# main.net
KiCad netlist of a schematic drawn in EAGLE
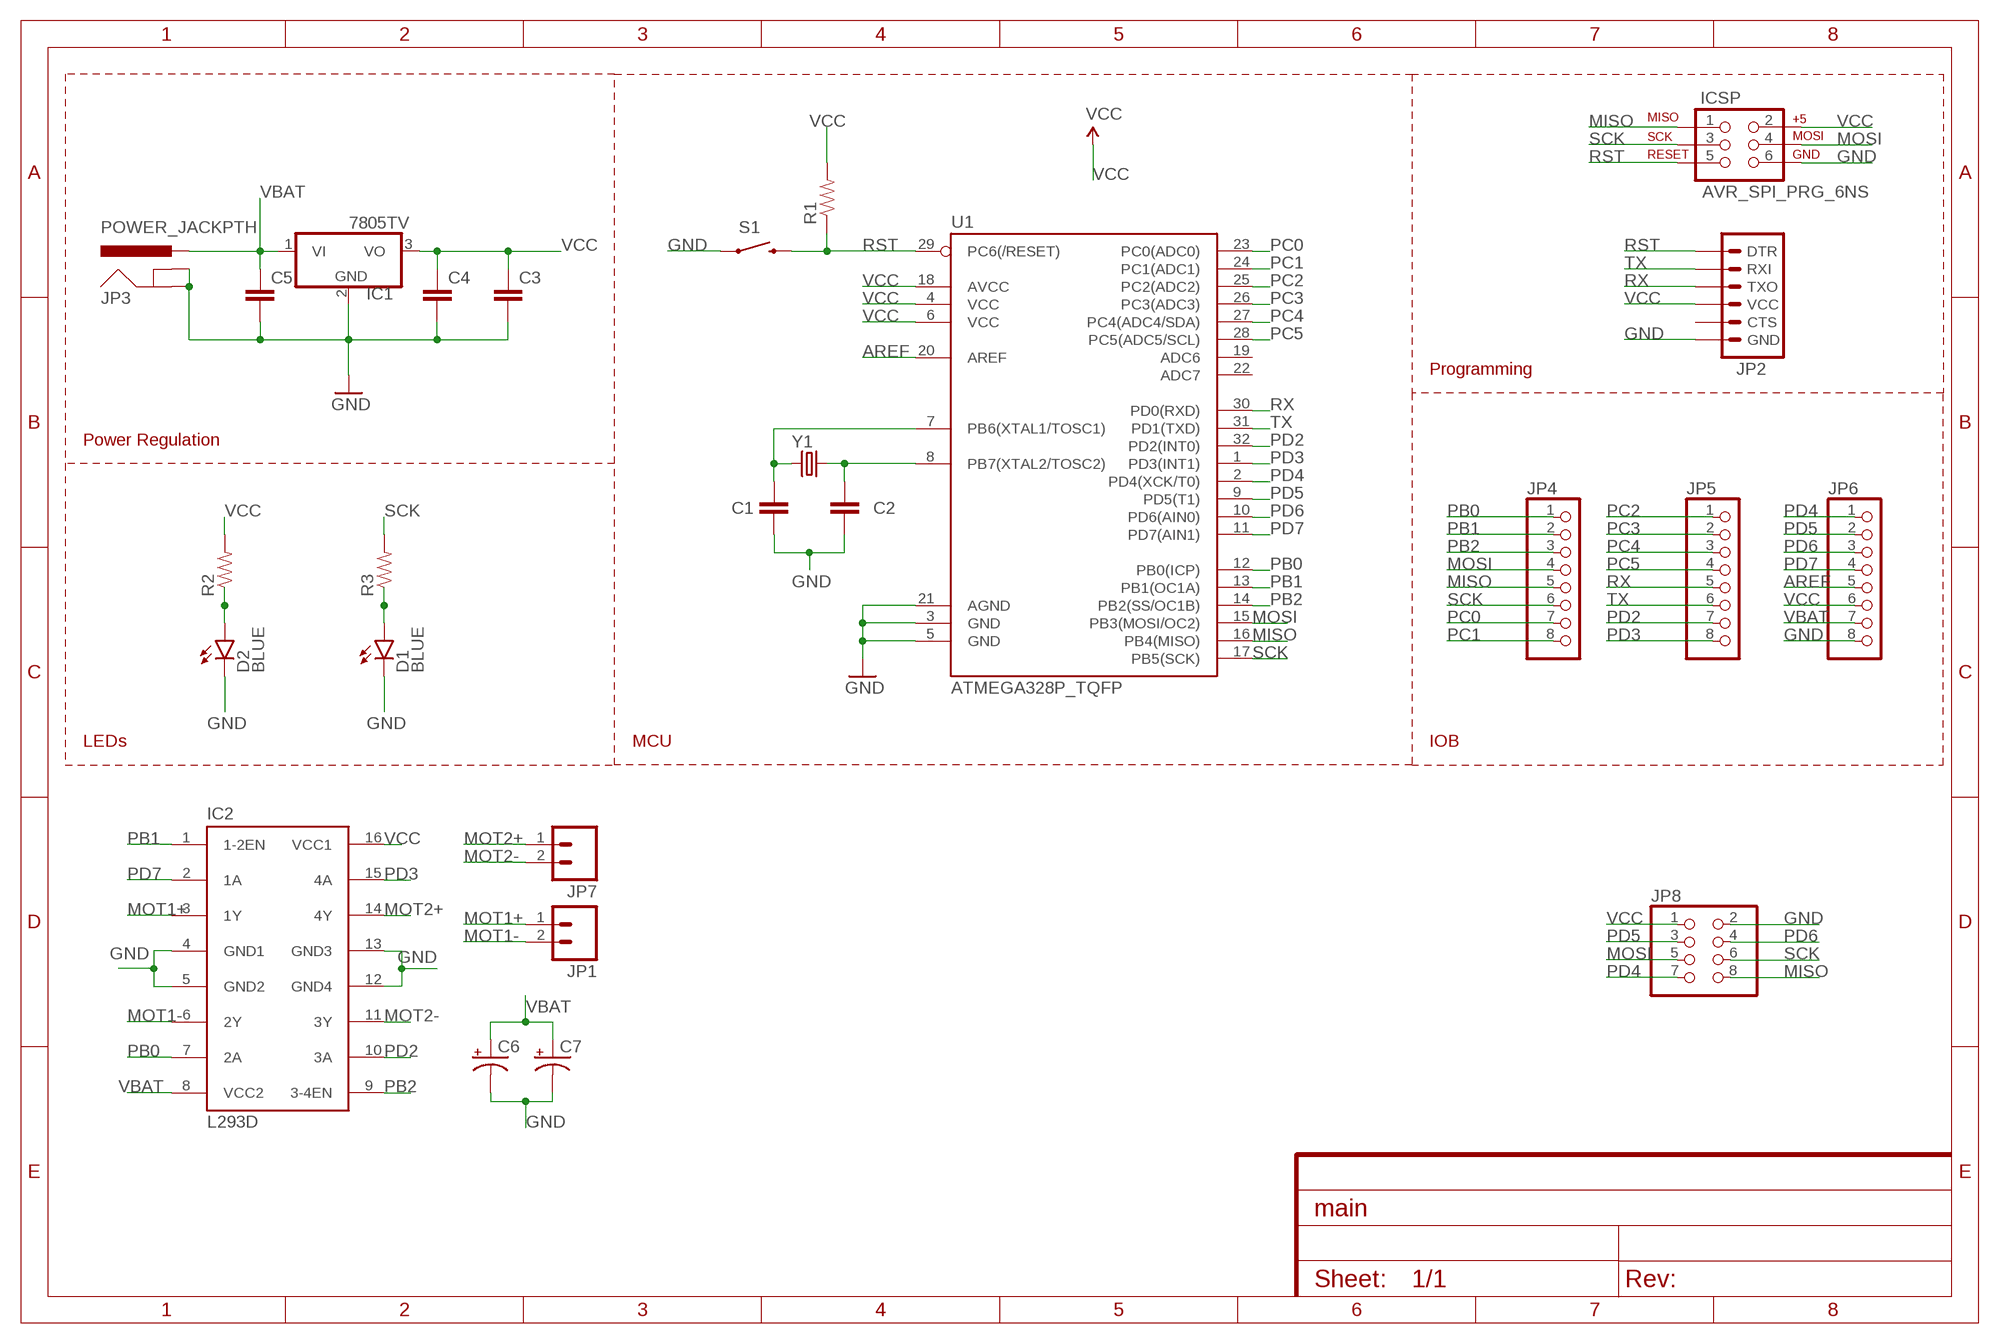
[diagram p0: schematic, sheet 1]

(export (version "E")
  (design (tool "Eeschema 10.0.6"))
  (components
    (comp (ref "C1")
      (value "CAP0805")
      (footprint "eagle-import:0805")
      (libsource (lib "eagle-import") (part "CAP0805"))
    )
    (comp (ref "C2")
      (value "CAP0805")
      (footprint "eagle-import:0805")
      (libsource (lib "eagle-import") (part "CAP0805"))
    )
    (comp (ref "C3")
      (value "CAP0805")
      (footprint "eagle-import:0805")
      (libsource (lib "eagle-import") (part "CAP0805"))
    )
    (comp (ref "C4")
      (value "CAP0805")
      (footprint "eagle-import:0805")
      (libsource (lib "eagle-import") (part "CAP0805"))
    )
    (comp (ref "C5")
      (value "CAP0805")
      (footprint "eagle-import:0805")
      (libsource (lib "eagle-import") (part "CAP0805"))
    )
    (comp (ref "C6")
      (value "CAP_POLPTH2")
      (footprint "eagle-import:CPOL-RADIAL-10UF-25V")
      (libsource (lib "eagle-import") (part "CAP_POLPTH2"))
    )
    (comp (ref "C7")
      (value "CAP_POLPTH2")
      (footprint "eagle-import:CPOL-RADIAL-10UF-25V")
      (libsource (lib "eagle-import") (part "CAP_POLPTH2"))
    )
    (comp (ref "D1")
      (value "BLUE")
      (footprint "eagle-import:LED-0603")
      (libsource (lib "eagle-import") (part "LED-BLUE0603"))
    )
    (comp (ref "D2")
      (value "BLUE")
      (footprint "eagle-import:LED-0603")
      (libsource (lib "eagle-import") (part "LED-BLUE0603"))
    )
    (comp (ref "IC1")
      (value "7805TV")
      (footprint "eagle-import:TO220V")
      (libsource (lib "eagle-import") (part "78TV05"))
    )
    (comp (ref "IC2")
      (value "L293D")
      (footprint "eagle-import:DIL16")
      (libsource (lib "eagle-import") (part "L293D"))
    )
    (comp (ref "ICSP")
      (value "AVR_SPI_PRG_6NS")
      (footprint "eagle-import:2X3-NS")
      (libsource (lib "eagle-import") (part "AVR_SPI_PRG_6NS"))
    )
    (comp (ref "JP1")
      (value "M025MM")
      (footprint "eagle-import:SCREWTERMINAL-5MM-2")
      (libsource (lib "eagle-import") (part "M025MM"))
    )
    (comp (ref "JP2")
      (value "ARDUINO_SERIAL_PROGRAMLOCK")
      (footprint "eagle-import:1X06_LOCK")
      (libsource (lib "eagle-import") (part "ARDUINO_SERIAL_PROGRAMLOCK"))
    )
    (comp (ref "JP3")
      (value "POWER_JACKPTH")
      (footprint "eagle-import:POWER_JACK_PTH")
      (libsource (lib "eagle-import") (part "POWER_JACKPTH"))
    )
    (comp (ref "JP4")
      (value "PINHD-1X8")
      (footprint "eagle-import:1X08")
      (libsource (lib "eagle-import") (part "PINHD-1X8"))
    )
    (comp (ref "JP5")
      (value "PINHD-1X8")
      (footprint "eagle-import:1X08")
      (libsource (lib "eagle-import") (part "PINHD-1X8"))
    )
    (comp (ref "JP6")
      (value "PINHD-1X8")
      (footprint "eagle-import:1X08")
      (libsource (lib "eagle-import") (part "PINHD-1X8"))
    )
    (comp (ref "JP7")
      (value "M025MM")
      (footprint "eagle-import:SCREWTERMINAL-5MM-2")
      (libsource (lib "eagle-import") (part "M025MM"))
    )
    (comp (ref "JP8")
      (value "PINHD-2X4")
      (footprint "eagle-import:2X04")
      (libsource (lib "eagle-import") (part "PINHD-2X4"))
    )
    (comp (ref "R1")
      (value "RESISTOR0805-RES")
      (footprint "eagle-import:0805")
      (libsource (lib "eagle-import") (part "RESISTOR0805-RES"))
    )
    (comp (ref "R2")
      (value "RESISTOR0805-RES")
      (footprint "eagle-import:0805")
      (libsource (lib "eagle-import") (part "RESISTOR0805-RES"))
    )
    (comp (ref "R3")
      (value "RESISTOR0805-RES")
      (footprint "eagle-import:0805")
      (libsource (lib "eagle-import") (part "RESISTOR0805-RES"))
    )
    (comp (ref "S1")
      (value "SWITCH-MOMENTARY-2SMD")
      (footprint "eagle-import:TACTILE-SWITCH-SMD")
      (libsource (lib "eagle-import") (part "SWITCH-MOMENTARY-2SMD"))
    )
    (comp (ref "U1")
      (value "ATMEGA328P_TQFP")
      (footprint "eagle-import:TQFP32-08")
      (libsource (lib "eagle-import") (part "ATMEGA328P_TQFP"))
    )
    (comp (ref "Y1")
      (value "CRYSTALHC49US")
      (footprint "eagle-import:HC49US")
      (libsource (lib "eagle-import") (part "CRYSTALHC49US"))
    )
  )
  (nets
    (net (code "1") (name "/AREF") (class "Default")
      (node (ref "JP6") (pin "5") (pinfunction "5_5") (pintype "passive"))
      (node (ref "U1") (pin "20") (pinfunction "AREF_20") (pintype "bidirectional"))
    )
    (net (code "2") (name "/MISO") (class "Default")
      (node (ref "ICSP") (pin "1") (pinfunction "1_1") (pintype "passive"))
      (node (ref "JP4") (pin "5") (pinfunction "5_5") (pintype "passive"))
      (node (ref "JP8") (pin "8") (pinfunction "8_8") (pintype "passive"))
      (node (ref "U1") (pin "16") (pinfunction "PB4(MISO)_16") (pintype "bidirectional"))
    )
    (net (code "3") (name "/MOSI") (class "Default")
      (node (ref "ICSP") (pin "4") (pinfunction "4_4") (pintype "passive"))
      (node (ref "JP4") (pin "4") (pinfunction "4_4") (pintype "passive"))
      (node (ref "JP8") (pin "5") (pinfunction "5_5") (pintype "passive"))
      (node (ref "U1") (pin "15") (pinfunction "PB3(MOSI/OC2)_15") (pintype "bidirectional"))
    )
    (net (code "4") (name "/MOT1+") (class "Default")
      (node (ref "IC2") (pin "3") (pinfunction "1Y_3") (pintype "output"))
      (node (ref "JP1") (pin "1") (pinfunction "1_1") (pintype "passive"))
    )
    (net (code "5") (name "/MOT1-") (class "Default")
      (node (ref "IC2") (pin "6") (pinfunction "2Y_6") (pintype "output"))
      (node (ref "JP1") (pin "2") (pinfunction "2_2") (pintype "passive"))
    )
    (net (code "6") (name "/MOT2+") (class "Default")
      (node (ref "IC2") (pin "14") (pinfunction "4Y_14") (pintype "output"))
      (node (ref "JP7") (pin "1") (pinfunction "1_1") (pintype "passive"))
    )
    (net (code "7") (name "/MOT2-") (class "Default")
      (node (ref "IC2") (pin "11") (pinfunction "3Y_11") (pintype "output"))
      (node (ref "JP7") (pin "2") (pinfunction "2_2") (pintype "passive"))
    )
    (net (code "8") (name "/PB0") (class "Default")
      (node (ref "IC2") (pin "7") (pinfunction "2A_7") (pintype "input"))
      (node (ref "JP4") (pin "1") (pinfunction "1_1") (pintype "passive"))
      (node (ref "U1") (pin "12") (pinfunction "PB0(ICP)_12") (pintype "bidirectional"))
    )
    (net (code "9") (name "/PB1") (class "Default")
      (node (ref "IC2") (pin "1") (pinfunction "1-2EN_1") (pintype "input"))
      (node (ref "JP4") (pin "2") (pinfunction "2_2") (pintype "passive"))
      (node (ref "U1") (pin "13") (pinfunction "PB1(OC1A)_13") (pintype "bidirectional"))
    )
    (net (code "10") (name "/PB2") (class "Default")
      (node (ref "IC2") (pin "9") (pinfunction "3-4EN_9") (pintype "input"))
      (node (ref "JP4") (pin "3") (pinfunction "3_3") (pintype "passive"))
      (node (ref "U1") (pin "14") (pinfunction "PB2(SS/OC1B)_14") (pintype "bidirectional"))
    )
    (net (code "11") (name "/PC0") (class "Default")
      (node (ref "JP4") (pin "7") (pinfunction "7_7") (pintype "passive"))
      (node (ref "U1") (pin "23") (pinfunction "PC0(ADC0)_23") (pintype "bidirectional"))
    )
    (net (code "12") (name "/PC1") (class "Default")
      (node (ref "JP4") (pin "8") (pinfunction "8_8") (pintype "passive"))
      (node (ref "U1") (pin "24") (pinfunction "PC1(ADC1)_24") (pintype "bidirectional"))
    )
    (net (code "13") (name "/PC2") (class "Default")
      (node (ref "JP5") (pin "1") (pinfunction "1_1") (pintype "passive"))
      (node (ref "U1") (pin "25") (pinfunction "PC2(ADC2)_25") (pintype "bidirectional"))
    )
    (net (code "14") (name "/PC3") (class "Default")
      (node (ref "JP5") (pin "2") (pinfunction "2_2") (pintype "passive"))
      (node (ref "U1") (pin "26") (pinfunction "PC3(ADC3)_26") (pintype "bidirectional"))
    )
    (net (code "15") (name "/PC4") (class "Default")
      (node (ref "JP5") (pin "3") (pinfunction "3_3") (pintype "passive"))
      (node (ref "U1") (pin "27") (pinfunction "PC4(ADC4/SDA)_27") (pintype "bidirectional"))
    )
    (net (code "16") (name "/PC5") (class "Default")
      (node (ref "JP5") (pin "4") (pinfunction "4_4") (pintype "passive"))
      (node (ref "U1") (pin "28") (pinfunction "PC5(ADC5/SCL)_28") (pintype "bidirectional"))
    )
    (net (code "17") (name "/PD2") (class "Default")
      (node (ref "IC2") (pin "10") (pinfunction "3A_10") (pintype "input"))
      (node (ref "JP5") (pin "7") (pinfunction "7_7") (pintype "passive"))
      (node (ref "U1") (pin "32") (pinfunction "PD2(INT0)_32") (pintype "bidirectional"))
    )
    (net (code "18") (name "/PD3") (class "Default")
      (node (ref "IC2") (pin "15") (pinfunction "4A_15") (pintype "input"))
      (node (ref "JP5") (pin "8") (pinfunction "8_8") (pintype "passive"))
      (node (ref "U1") (pin "1") (pinfunction "PD3(INT1)_1") (pintype "bidirectional"))
    )
    (net (code "19") (name "/PD4") (class "Default")
      (node (ref "JP6") (pin "1") (pinfunction "1_1") (pintype "passive"))
      (node (ref "JP8") (pin "7") (pinfunction "7_7") (pintype "passive"))
      (node (ref "U1") (pin "2") (pinfunction "PD4(XCK/T0)_2") (pintype "bidirectional"))
    )
    (net (code "20") (name "/PD5") (class "Default")
      (node (ref "JP6") (pin "2") (pinfunction "2_2") (pintype "passive"))
      (node (ref "JP8") (pin "3") (pinfunction "3_3") (pintype "passive"))
      (node (ref "U1") (pin "9") (pinfunction "PD5(T1)_9") (pintype "bidirectional"))
    )
    (net (code "21") (name "/PD6") (class "Default")
      (node (ref "JP6") (pin "3") (pinfunction "3_3") (pintype "passive"))
      (node (ref "JP8") (pin "4") (pinfunction "4_4") (pintype "passive"))
      (node (ref "U1") (pin "10") (pinfunction "PD6(AIN0)_10") (pintype "bidirectional"))
    )
    (net (code "22") (name "/PD7") (class "Default")
      (node (ref "IC2") (pin "2") (pinfunction "1A_2") (pintype "input"))
      (node (ref "JP6") (pin "4") (pinfunction "4_4") (pintype "passive"))
      (node (ref "U1") (pin "11") (pinfunction "PD7(AIN1)_11") (pintype "bidirectional"))
    )
    (net (code "23") (name "/RST") (class "Default")
      (node (ref "ICSP") (pin "5") (pinfunction "5_5") (pintype "passive"))
      (node (ref "JP2") (pin "1") (pinfunction "DTR_1") (pintype "passive"))
      (node (ref "R1") (pin "1") (pinfunction "1_1") (pintype "passive"))
      (node (ref "S1") (pin "3") (pinfunction "2_3") (pintype "passive"))
      (node (ref "U1") (pin "29") (pinfunction "PC6(/RESET)_29") (pintype "bidirectional"))
    )
    (net (code "24") (name "/RX") (class "Default")
      (node (ref "JP2") (pin "3") (pinfunction "TXO_3") (pintype "passive"))
      (node (ref "JP5") (pin "5") (pinfunction "5_5") (pintype "passive"))
      (node (ref "U1") (pin "30") (pinfunction "PD0(RXD)_30") (pintype "bidirectional"))
    )
    (net (code "25") (name "/SCK") (class "Default")
      (node (ref "ICSP") (pin "3") (pinfunction "3_3") (pintype "passive"))
      (node (ref "JP4") (pin "6") (pinfunction "6_6") (pintype "passive"))
      (node (ref "JP8") (pin "6") (pinfunction "6_6") (pintype "passive"))
      (node (ref "R3") (pin "2") (pinfunction "2_2") (pintype "passive"))
      (node (ref "U1") (pin "17") (pinfunction "PB5(SCK)_17") (pintype "bidirectional"))
    )
    (net (code "26") (name "/TX") (class "Default")
      (node (ref "JP2") (pin "2") (pinfunction "RXI_2") (pintype "passive"))
      (node (ref "JP5") (pin "6") (pinfunction "6_6") (pintype "passive"))
      (node (ref "U1") (pin "31") (pinfunction "PD1(TXD)_31") (pintype "bidirectional"))
    )
    (net (code "27") (name "/VBAT") (class "Default")
      (node (ref "C5") (pin "1") (pinfunction "1_1") (pintype "passive"))
      (node (ref "C6") (pin "1") (pinfunction "+_1") (pintype "passive"))
      (node (ref "C7") (pin "1") (pinfunction "+_1") (pintype "passive"))
      (node (ref "IC1") (pin "1") (pinfunction "VI_1") (pintype "input"))
      (node (ref "IC2") (pin "8") (pinfunction "VCC2_8") (pintype "power_in"))
      (node (ref "JP3") (pin "PWR") (pinfunction "PWR_PWR") (pintype "bidirectional"))
      (node (ref "JP6") (pin "7") (pinfunction "7_7") (pintype "passive"))
    )
    (net (code "28") (name "GND") (class "Default")
      (node (ref "C1") (pin "2") (pinfunction "2_2") (pintype "passive"))
      (node (ref "C2") (pin "2") (pinfunction "2_2") (pintype "passive"))
      (node (ref "C3") (pin "2") (pinfunction "2_2") (pintype "passive"))
      (node (ref "C4") (pin "2") (pinfunction "2_2") (pintype "passive"))
      (node (ref "C5") (pin "2") (pinfunction "2_2") (pintype "passive"))
      (node (ref "C6") (pin "2") (pinfunction "-_2") (pintype "passive"))
      (node (ref "C7") (pin "2") (pinfunction "-_2") (pintype "passive"))
      (node (ref "D1") (pin "C") (pinfunction "C_C") (pintype "passive"))
      (node (ref "D2") (pin "C") (pinfunction "C_C") (pintype "passive"))
      (node (ref "IC1") (pin "2") (pinfunction "GND_2") (pintype "passive"))
      (node (ref "IC2") (pin "12") (pinfunction "GND4_12") (pintype "power_in"))
      (node (ref "IC2") (pin "13") (pinfunction "GND3_13") (pintype "power_in"))
      (node (ref "IC2") (pin "4") (pinfunction "GND1_4") (pintype "power_in"))
      (node (ref "IC2") (pin "5") (pinfunction "GND2_5") (pintype "power_in"))
      (node (ref "ICSP") (pin "6") (pinfunction "6_6") (pintype "passive"))
      (node (ref "JP2") (pin "6") (pinfunction "GND_6") (pintype "passive"))
      (node (ref "JP3") (pin "GND") (pinfunction "GND_GND") (pintype "bidirectional"))
      (node (ref "JP3") (pin "GNDBREAK") (pinfunction "GNDBREAK_GNDBREAK") (pintype "bidirectional"))
      (node (ref "JP6") (pin "8") (pinfunction "8_8") (pintype "passive"))
      (node (ref "JP8") (pin "2") (pinfunction "2_2") (pintype "passive"))
      (node (ref "S1") (pin "1") (pinfunction "1_1") (pintype "passive"))
      (node (ref "U1") (pin "21") (pinfunction "AGND_21") (pintype "bidirectional"))
      (node (ref "U1") (pin "3") (pinfunction "GND_3") (pintype "bidirectional"))
      (node (ref "U1") (pin "5") (pinfunction "GND_5") (pintype "bidirectional"))
    )
    (net (code "29") (name "Net-(D1-PadA)") (class "Default")
      (node (ref "D1") (pin "A") (pinfunction "A_A") (pintype "passive"))
      (node (ref "R3") (pin "1") (pinfunction "1_1") (pintype "passive"))
    )
    (net (code "30") (name "Net-(D2-PadA)") (class "Default")
      (node (ref "D2") (pin "A") (pinfunction "A_A") (pintype "passive"))
      (node (ref "R2") (pin "1") (pinfunction "1_1") (pintype "passive"))
    )
    (net (code "31") (name "Net-(U1-PB6(XTAL1{slash}TOSC1))") (class "Default")
      (node (ref "C1") (pin "1") (pinfunction "1_1") (pintype "passive"))
      (node (ref "U1") (pin "7") (pinfunction "PB6(XTAL1/TOSC1)_7") (pintype "bidirectional"))
      (node (ref "Y1") (pin "2") (pinfunction "2_2") (pintype "passive"))
    )
    (net (code "32") (name "Net-(U1-PB7(XTAL2{slash}TOSC2))") (class "Default")
      (node (ref "C2") (pin "1") (pinfunction "1_1") (pintype "passive"))
      (node (ref "U1") (pin "8") (pinfunction "PB7(XTAL2/TOSC2)_8") (pintype "bidirectional"))
      (node (ref "Y1") (pin "1") (pinfunction "1_1") (pintype "passive"))
    )
    (net (code "33") (name "VCC") (class "Default")
      (node (ref "C3") (pin "1") (pinfunction "1_1") (pintype "passive"))
      (node (ref "C4") (pin "1") (pinfunction "1_1") (pintype "passive"))
      (node (ref "IC1") (pin "3") (pinfunction "VO_3") (pintype "passive"))
      (node (ref "IC2") (pin "16") (pinfunction "VCC1_16") (pintype "power_in"))
      (node (ref "ICSP") (pin "2") (pinfunction "2_2") (pintype "passive"))
      (node (ref "JP2") (pin "4") (pinfunction "VCC_4") (pintype "passive"))
      (node (ref "JP6") (pin "6") (pinfunction "6_6") (pintype "passive"))
      (node (ref "JP8") (pin "1") (pinfunction "1_1") (pintype "passive"))
      (node (ref "R1") (pin "2") (pinfunction "2_2") (pintype "passive"))
      (node (ref "R2") (pin "2") (pinfunction "2_2") (pintype "passive"))
      (node (ref "U1") (pin "18") (pinfunction "AVCC_18") (pintype "bidirectional"))
      (node (ref "U1") (pin "4") (pinfunction "VCC_4") (pintype "bidirectional"))
      (node (ref "U1") (pin "6") (pinfunction "VCC_6") (pintype "bidirectional"))
    )
    (net (code "34") (name "unconnected-(JP2-CTS-Pad5)") (class "Default")
      (node (ref "JP2") (pin "5") (pinfunction "CTS_5") (pintype "passive"))
    )
    (net (code "35") (name "unconnected-(U1-ADC6-Pad19)") (class "Default")
      (node (ref "U1") (pin "19") (pinfunction "ADC6_19") (pintype "bidirectional"))
    )
    (net (code "36") (name "unconnected-(U1-ADC7-Pad22)") (class "Default")
      (node (ref "U1") (pin "22") (pinfunction "ADC7_22") (pintype "bidirectional"))
    )
  )
)
